# WS2811Controller.net
KiCad netlist of a schematic drawn in EAGLE
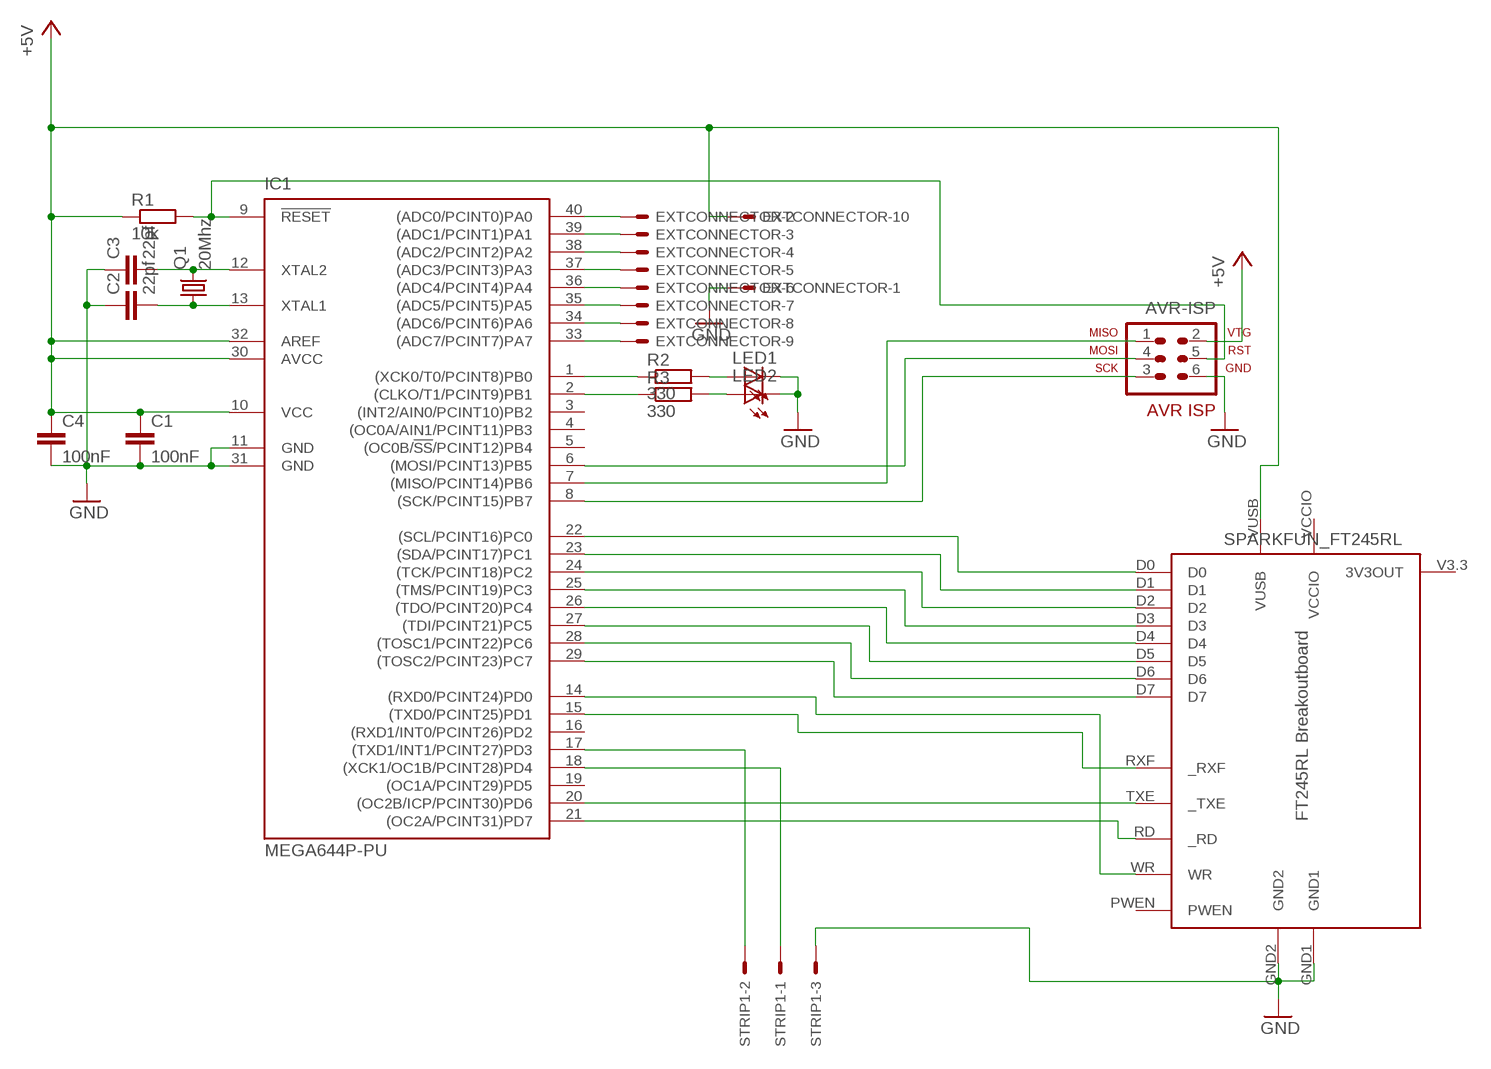
[diagram p0: schematic, sheet 1]

(export (version "E")
  (design (tool "Eeschema 10.0.6"))
  (components
    (comp (ref "AVR-ISP")
      (value "AVR-ISP-6")
      (footprint "eagle-import:AVR-ISP-6")
      (libsource (lib "eagle-import") (part "AVR-ISP-6"))
    )
    (comp (ref "C1")
      (value "100nF")
      (footprint "eagle-import:C025-025X050")
      (libsource (lib "eagle-import") (part "C-EU025-025X050"))
    )
    (comp (ref "C2")
      (value "22pf")
      (footprint "eagle-import:C025-025X050")
      (libsource (lib "eagle-import") (part "C-EU025-025X050"))
    )
    (comp (ref "C3")
      (value "22pf")
      (footprint "eagle-import:C025-025X050")
      (libsource (lib "eagle-import") (part "C-EU025-025X050"))
    )
    (comp (ref "C4")
      (value "100nF")
      (footprint "eagle-import:C025-025X050")
      (libsource (lib "eagle-import") (part "C-EU025-025X050"))
    )
    (comp (ref "EXTCONNECTOR")
      (value "22-27-2101-10")
      (footprint "eagle-import:6410-10")
      (libsource (lib "eagle-import") (part "22-?-1027-2101"))
    )
    (comp (ref "IC1")
      (value "MEGA644P-PU")
      (footprint "eagle-import:DIL40")
      (libsource (lib "eagle-import") (part "MEGA164P/324P/644P-PU"))
    )
    (comp (ref "LED1")
      (value "LED3MM")
      (footprint "eagle-import:LED3MM")
      (libsource (lib "eagle-import") (part "LED3MM"))
    )
    (comp (ref "LED2")
      (value "LED3MM")
      (footprint "eagle-import:LED3MM")
      (libsource (lib "eagle-import") (part "LED3MM"))
    )
    (comp (ref "Q1")
      (value "20Mhz")
      (footprint "eagle-import:HC49U-V")
      (libsource (lib "eagle-import") (part "CRYSTALHC49U-V"))
    )
    (comp (ref "R1")
      (value "10k")
      (footprint "eagle-import:0207_10")
      (libsource (lib "eagle-import") (part "R-EU_0207/10"))
    )
    (comp (ref "R2")
      (value "330")
      (footprint "eagle-import:0207_10")
      (libsource (lib "eagle-import") (part "R-EU_0207/10"))
    )
    (comp (ref "R3")
      (value "330")
      (footprint "eagle-import:0207_10")
      (libsource (lib "eagle-import") (part "R-EU_0207/10"))
    )
    (comp (ref "SPARKFUN_FT245RL")
      (value "FT245RL_BREAKOUTBOARD")
      (footprint "eagle-import:SPARKFUN_FT245RL_BOARD")
      (libsource (lib "eagle-import") (part "FT245RL_BREAKOUTBOARD"))
    )
    (comp (ref "STRIP1")
      (value "22-27-2031-03")
      (footprint "eagle-import:6410-03")
      (libsource (lib "eagle-import") (part "22-?-0327-2031"))
    )
  )
  (nets
    (net (code "1") (name "+5V") (class "Default")
      (node (ref "AVR-ISP") (pin "2") (pinfunction "2_2") (pintype "passive"))
      (node (ref "C1") (pin "1") (pinfunction "1_1") (pintype "passive"))
      (node (ref "C4") (pin "1") (pinfunction "1_1") (pintype "passive"))
      (node (ref "EXTCONNECTOR") (pin "10") (pinfunction "S_10") (pintype "passive"))
      (node (ref "IC1") (pin "10") (pinfunction "VCC_10") (pintype "power_in"))
      (node (ref "IC1") (pin "30") (pinfunction "AVCC_30") (pintype "power_in"))
      (node (ref "IC1") (pin "32") (pinfunction "AREF_32") (pintype "power_in"))
      (node (ref "R1") (pin "1") (pinfunction "1_1") (pintype "passive"))
      (node (ref "SPARKFUN_FT245RL") (pin "VUSB") (pinfunction "VUSB_VUSB") (pintype "bidirectional"))
    )
    (net (code "2") (name "/VCCIO") (class "Default")
      (node (ref "SPARKFUN_FT245RL") (pin "VCCIO") (pinfunction "VCCIO_VCCIO") (pintype "power_in"))
    )
    (net (code "3") (name "GND") (class "Default")
      (node (ref "AVR-ISP") (pin "6") (pinfunction "6_6") (pintype "passive"))
      (node (ref "C1") (pin "2") (pinfunction "2_2") (pintype "passive"))
      (node (ref "C2") (pin "1") (pinfunction "1_1") (pintype "passive"))
      (node (ref "C3") (pin "1") (pinfunction "1_1") (pintype "passive"))
      (node (ref "C4") (pin "2") (pinfunction "2_2") (pintype "passive"))
      (node (ref "EXTCONNECTOR") (pin "1") (pinfunction "S_1") (pintype "passive"))
      (node (ref "IC1") (pin "11") (pinfunction "GND_11") (pintype "power_in"))
      (node (ref "IC1") (pin "31") (pinfunction "GND_31") (pintype "power_in"))
      (node (ref "LED1") (pin "K") (pinfunction "C_K") (pintype "passive"))
      (node (ref "LED2") (pin "K") (pinfunction "C_K") (pintype "passive"))
      (node (ref "SPARKFUN_FT245RL") (pin "GND1") (pinfunction "GND1_GND1") (pintype "power_in"))
      (node (ref "SPARKFUN_FT245RL") (pin "GND2") (pinfunction "GND2_GND2") (pintype "power_in"))
      (node (ref "STRIP1") (pin "3") (pinfunction "S_3") (pintype "passive"))
    )
    (net (code "4") (name "Net-(EXTCONNECTORC-S)") (class "Default")
      (node (ref "EXTCONNECTOR") (pin "2") (pinfunction "S_2") (pintype "passive"))
      (node (ref "IC1") (pin "40") (pinfunction "(ADC0/PCINT0)PA0_40") (pintype "bidirectional"))
    )
    (net (code "5") (name "Net-(EXTCONNECTORD-S)") (class "Default")
      (node (ref "EXTCONNECTOR") (pin "3") (pinfunction "S_3") (pintype "passive"))
      (node (ref "IC1") (pin "39") (pinfunction "(ADC1/PCINT1)PA1_39") (pintype "bidirectional"))
    )
    (net (code "6") (name "Net-(EXTCONNECTORE-S)") (class "Default")
      (node (ref "EXTCONNECTOR") (pin "4") (pinfunction "S_4") (pintype "passive"))
      (node (ref "IC1") (pin "38") (pinfunction "(ADC2/PCINT2)PA2_38") (pintype "bidirectional"))
    )
    (net (code "7") (name "Net-(EXTCONNECTORF-S)") (class "Default")
      (node (ref "EXTCONNECTOR") (pin "5") (pinfunction "S_5") (pintype "passive"))
      (node (ref "IC1") (pin "37") (pinfunction "(ADC3/PCINT3)PA3_37") (pintype "bidirectional"))
    )
    (net (code "8") (name "Net-(EXTCONNECTORG-S)") (class "Default")
      (node (ref "EXTCONNECTOR") (pin "6") (pinfunction "S_6") (pintype "passive"))
      (node (ref "IC1") (pin "36") (pinfunction "(ADC4/PCINT4)PA4_36") (pintype "bidirectional"))
    )
    (net (code "9") (name "Net-(EXTCONNECTORH-S)") (class "Default")
      (node (ref "EXTCONNECTOR") (pin "7") (pinfunction "S_7") (pintype "passive"))
      (node (ref "IC1") (pin "35") (pinfunction "(ADC5/PCINT5)PA5_35") (pintype "bidirectional"))
    )
    (net (code "10") (name "Net-(EXTCONNECTORI-S)") (class "Default")
      (node (ref "EXTCONNECTOR") (pin "8") (pinfunction "S_8") (pintype "passive"))
      (node (ref "IC1") (pin "34") (pinfunction "(ADC6/PCINT6)PA6_34") (pintype "bidirectional"))
    )
    (net (code "11") (name "Net-(EXTCONNECTORJ-S)") (class "Default")
      (node (ref "EXTCONNECTOR") (pin "9") (pinfunction "S_9") (pintype "passive"))
      (node (ref "IC1") (pin "33") (pinfunction "(ADC7/PCINT7)PA7_33") (pintype "bidirectional"))
    )
    (net (code "12") (name "Net-(IC1-(CLKO{slash}T1{slash}PCINT9)PB1)") (class "Default")
      (node (ref "IC1") (pin "2") (pinfunction "(CLKO/T1/PCINT9)PB1_2") (pintype "bidirectional"))
      (node (ref "R3") (pin "1") (pinfunction "1_1") (pintype "passive"))
    )
    (net (code "13") (name "Net-(IC1-(MISO{slash}PCINT14)PB6)") (class "Default")
      (node (ref "AVR-ISP") (pin "1") (pinfunction "1_1") (pintype "passive"))
      (node (ref "IC1") (pin "7") (pinfunction "(MISO/PCINT14)PB6_7") (pintype "bidirectional"))
    )
    (net (code "14") (name "Net-(IC1-(MOSI{slash}PCINT13)PB5)") (class "Default")
      (node (ref "AVR-ISP") (pin "4") (pinfunction "4_4") (pintype "passive"))
      (node (ref "IC1") (pin "6") (pinfunction "(MOSI/PCINT13)PB5_6") (pintype "bidirectional"))
    )
    (net (code "15") (name "Net-(IC1-(OC2A{slash}PCINT31)PD7)") (class "Default")
      (node (ref "IC1") (pin "21") (pinfunction "(OC2A/PCINT31)PD7_21") (pintype "bidirectional"))
      (node (ref "SPARKFUN_FT245RL") (pin "RD") (pinfunction "_RD_RD") (pintype "bidirectional"))
    )
    (net (code "16") (name "Net-(IC1-(OC2B{slash}ICP{slash}PCINT30)PD6)") (class "Default")
      (node (ref "IC1") (pin "20") (pinfunction "(OC2B/ICP/PCINT30)PD6_20") (pintype "bidirectional"))
      (node (ref "SPARKFUN_FT245RL") (pin "TXE") (pinfunction "_TXE_TXE") (pintype "bidirectional"))
    )
    (net (code "17") (name "Net-(IC1-(RXD0{slash}PCINT24)PD0)") (class "Default")
      (node (ref "IC1") (pin "14") (pinfunction "(RXD0/PCINT24)PD0_14") (pintype "bidirectional"))
      (node (ref "SPARKFUN_FT245RL") (pin "WR") (pinfunction "WR_WR") (pintype "bidirectional"))
    )
    (net (code "18") (name "Net-(IC1-(SCK{slash}PCINT15)PB7)") (class "Default")
      (node (ref "AVR-ISP") (pin "3") (pinfunction "3_3") (pintype "passive"))
      (node (ref "IC1") (pin "8") (pinfunction "(SCK/PCINT15)PB7_8") (pintype "bidirectional"))
    )
    (net (code "19") (name "Net-(IC1-(SCL{slash}PCINT16)PC0)") (class "Default")
      (node (ref "IC1") (pin "22") (pinfunction "(SCL/PCINT16)PC0_22") (pintype "bidirectional"))
      (node (ref "SPARKFUN_FT245RL") (pin "D0") (pinfunction "D0_D0") (pintype "output"))
    )
    (net (code "20") (name "Net-(IC1-(SDA{slash}PCINT17)PC1)") (class "Default")
      (node (ref "IC1") (pin "23") (pinfunction "(SDA/PCINT17)PC1_23") (pintype "bidirectional"))
      (node (ref "SPARKFUN_FT245RL") (pin "D1") (pinfunction "D1_D1") (pintype "input"))
    )
    (net (code "21") (name "Net-(IC1-(TCK{slash}PCINT18)PC2)") (class "Default")
      (node (ref "IC1") (pin "24") (pinfunction "(TCK/PCINT18)PC2_24") (pintype "bidirectional"))
      (node (ref "SPARKFUN_FT245RL") (pin "D2") (pinfunction "D2_D2") (pintype "output"))
    )
    (net (code "22") (name "Net-(IC1-(TDI{slash}PCINT21)PC5)") (class "Default")
      (node (ref "IC1") (pin "27") (pinfunction "(TDI/PCINT21)PC5_27") (pintype "bidirectional"))
      (node (ref "SPARKFUN_FT245RL") (pin "D5") (pinfunction "D5_D5") (pintype "input"))
    )
    (net (code "23") (name "Net-(IC1-(TDO{slash}PCINT20)PC4)") (class "Default")
      (node (ref "IC1") (pin "26") (pinfunction "(TDO/PCINT20)PC4_26") (pintype "bidirectional"))
      (node (ref "SPARKFUN_FT245RL") (pin "D4") (pinfunction "D4_D4") (pintype "output"))
    )
    (net (code "24") (name "Net-(IC1-(TMS{slash}PCINT19)PC3)") (class "Default")
      (node (ref "IC1") (pin "25") (pinfunction "(TMS/PCINT19)PC3_25") (pintype "bidirectional"))
      (node (ref "SPARKFUN_FT245RL") (pin "D3") (pinfunction "D3_D3") (pintype "input"))
    )
    (net (code "25") (name "Net-(IC1-(TOSC1{slash}PCINT22)PC6)") (class "Default")
      (node (ref "IC1") (pin "28") (pinfunction "(TOSC1/PCINT22)PC6_28") (pintype "bidirectional"))
      (node (ref "SPARKFUN_FT245RL") (pin "D6") (pinfunction "D6_D6") (pintype "input"))
    )
    (net (code "26") (name "Net-(IC1-(TOSC2{slash}PCINT23)PC7)") (class "Default")
      (node (ref "IC1") (pin "29") (pinfunction "(TOSC2/PCINT23)PC7_29") (pintype "bidirectional"))
      (node (ref "SPARKFUN_FT245RL") (pin "D7") (pinfunction "D7_D7") (pintype "input"))
    )
    (net (code "27") (name "Net-(IC1-(TXD0{slash}PCINT25)PD1)") (class "Default")
      (node (ref "IC1") (pin "15") (pinfunction "(TXD0/PCINT25)PD1_15") (pintype "bidirectional"))
      (node (ref "SPARKFUN_FT245RL") (pin "RXF") (pinfunction "_RXF_RXF") (pintype "bidirectional"))
    )
    (net (code "28") (name "Net-(IC1-(TXD1{slash}INT1{slash}PCINT27)PD3)") (class "Default")
      (node (ref "IC1") (pin "17") (pinfunction "(TXD1/INT1/PCINT27)PD3_17") (pintype "bidirectional"))
      (node (ref "STRIP1") (pin "2") (pinfunction "S_2") (pintype "passive"))
    )
    (net (code "29") (name "Net-(IC1-(XCK0{slash}T0{slash}PCINT8)PB0)") (class "Default")
      (node (ref "IC1") (pin "1") (pinfunction "(XCK0/T0/PCINT8)PB0_1") (pintype "bidirectional"))
      (node (ref "R2") (pin "1") (pinfunction "1_1") (pintype "passive"))
    )
    (net (code "30") (name "Net-(IC1-(XCK1{slash}OC1B{slash}PCINT28)PD4)") (class "Default")
      (node (ref "IC1") (pin "18") (pinfunction "(XCK1/OC1B/PCINT28)PD4_18") (pintype "bidirectional"))
      (node (ref "STRIP1") (pin "1") (pinfunction "S_1") (pintype "passive"))
    )
    (net (code "31") (name "Net-(IC1-XTAL1)") (class "Default")
      (node (ref "C2") (pin "2") (pinfunction "2_2") (pintype "passive"))
      (node (ref "IC1") (pin "13") (pinfunction "XTAL1_13") (pintype "input"))
      (node (ref "Q1") (pin "1") (pinfunction "1_1") (pintype "passive"))
    )
    (net (code "32") (name "Net-(IC1-XTAL2)") (class "Default")
      (node (ref "C3") (pin "2") (pinfunction "2_2") (pintype "passive"))
      (node (ref "IC1") (pin "12") (pinfunction "XTAL2_12") (pintype "output"))
      (node (ref "Q1") (pin "2") (pinfunction "2_2") (pintype "passive"))
    )
    (net (code "33") (name "Net-(IC1-~{RESET})") (class "Default")
      (node (ref "AVR-ISP") (pin "5") (pinfunction "5_5") (pintype "passive"))
      (node (ref "IC1") (pin "9") (pinfunction "~{RESET}_9") (pintype "input"))
      (node (ref "R1") (pin "2") (pinfunction "2_2") (pintype "passive"))
    )
    (net (code "34") (name "Net-(LED1-PadA)") (class "Default")
      (node (ref "LED1") (pin "A") (pinfunction "A_A") (pintype "passive"))
      (node (ref "R2") (pin "2") (pinfunction "2_2") (pintype "passive"))
    )
    (net (code "35") (name "Net-(LED2-PadA)") (class "Default")
      (node (ref "LED2") (pin "A") (pinfunction "A_A") (pintype "passive"))
      (node (ref "R3") (pin "2") (pinfunction "2_2") (pintype "passive"))
    )
    (net (code "36") (name "unconnected-(IC1-(INT2{slash}AIN0{slash}PCINT10)PB2-Pad3)") (class "Default")
      (node (ref "IC1") (pin "3") (pinfunction "(INT2/AIN0/PCINT10)PB2_3") (pintype "bidirectional"))
    )
    (net (code "37") (name "unconnected-(IC1-(OC0A{slash}AIN1{slash}PCINT11)PB3-Pad4)") (class "Default")
      (node (ref "IC1") (pin "4") (pinfunction "(OC0A/AIN1/PCINT11)PB3_4") (pintype "bidirectional"))
    )
    (net (code "38") (name "unconnected-(IC1-(OC0B{slash}~{SS}{slash}PCINT12)PB4-Pad5)") (class "Default")
      (node (ref "IC1") (pin "5") (pinfunction "(OC0B/~{SS}/PCINT12)PB4_5") (pintype "bidirectional"))
    )
    (net (code "39") (name "unconnected-(IC1-(OC1A{slash}PCINT29)PD5-Pad19)") (class "Default")
      (node (ref "IC1") (pin "19") (pinfunction "(OC1A/PCINT29)PD5_19") (pintype "bidirectional"))
    )
    (net (code "40") (name "unconnected-(IC1-(RXD1{slash}INT0{slash}PCINT26)PD2-Pad16)") (class "Default")
      (node (ref "IC1") (pin "16") (pinfunction "(RXD1/INT0/PCINT26)PD2_16") (pintype "bidirectional"))
    )
    (net (code "41") (name "unconnected-(SPARKFUN_FT245RL-3V3OUT-PadV3.3)") (class "Default")
      (node (ref "SPARKFUN_FT245RL") (pin "V3.3") (pinfunction "3V3OUT_V3.3") (pintype "output"))
    )
    (net (code "42") (name "unconnected-(SPARKFUN_FT245RL-PadPWEN)") (class "Default")
      (node (ref "SPARKFUN_FT245RL") (pin "PWEN") (pinfunction "PWEN_PWEN") (pintype "bidirectional"))
    )
  )
)
